# Sheet1.net
KiCad netlist of a schematic drawn in Altium Designer
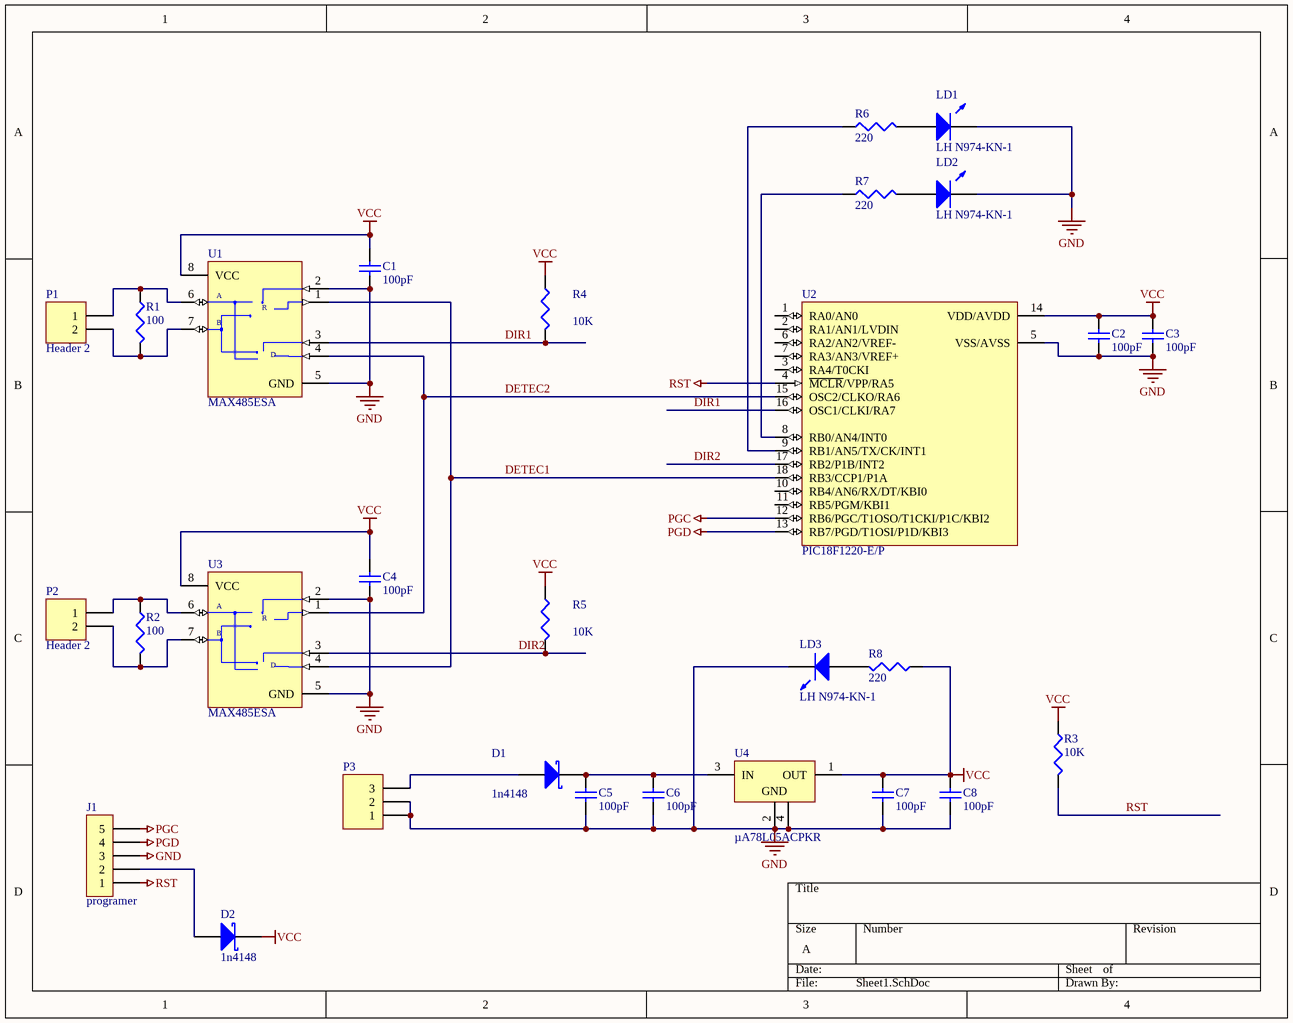
[diagram p0: Sheet1.SchDoc]

(export (version "E")
  (design (tool "Eeschema 10.0.6"))
  (components
    (comp (ref "C1")
      (value "100pF")
      (footprint "RESC2012L")
      (description "Capacitor (Semiconductor SIM Model)")
      (fields (field (name "Comment") "Cap Semi") (field (name "PUBLISHER") "Altium Limited"))
      (libsource (lib "Miscellaneous Devices") (part "Cap Semi"))
    )
    (comp (ref "C2")
      (value "100pF")
      (footprint "RESC2012L")
      (description "Capacitor (Semiconductor SIM Model)")
      (fields (field (name "Comment") "Cap Semi") (field (name "PUBLISHER") "Altium Limited"))
      (libsource (lib "Miscellaneous Devices") (part "Cap Semi"))
    )
    (comp (ref "C3")
      (value "100pF")
      (footprint "RESC2012L")
      (description "Capacitor (Semiconductor SIM Model)")
      (fields (field (name "Comment") "Cap Semi") (field (name "PUBLISHER") "Altium Limited"))
      (libsource (lib "Miscellaneous Devices") (part "Cap Semi"))
    )
    (comp (ref "C4")
      (value "100pF")
      (footprint "RESC2012L")
      (description "Capacitor (Semiconductor SIM Model)")
      (fields (field (name "Comment") "Cap Semi") (field (name "PUBLISHER") "Altium Limited"))
      (libsource (lib "Miscellaneous Devices") (part "Cap Semi"))
    )
    (comp (ref "C5")
      (value "100pF")
      (footprint "RESC2012L")
      (description "Capacitor (Semiconductor SIM Model)")
      (fields (field (name "Comment") "Cap Semi") (field (name "PUBLISHER") "Altium Limited"))
      (libsource (lib "Miscellaneous Devices") (part "Cap Semi"))
    )
    (comp (ref "C6")
      (value "100pF")
      (footprint "RESC2012L")
      (description "Capacitor (Semiconductor SIM Model)")
      (fields (field (name "Comment") "Cap Semi") (field (name "PUBLISHER") "Altium Limited"))
      (libsource (lib "Miscellaneous Devices") (part "Cap Semi"))
    )
    (comp (ref "C7")
      (value "100pF")
      (footprint "RESC2012L")
      (description "Capacitor (Semiconductor SIM Model)")
      (fields (field (name "Comment") "Cap Semi") (field (name "PUBLISHER") "Altium Limited"))
      (libsource (lib "Miscellaneous Devices") (part "Cap Semi"))
    )
    (comp (ref "C8")
      (value "100pF")
      (footprint "RESC2012L")
      (description "Capacitor (Semiconductor SIM Model)")
      (fields (field (name "Comment") "Cap Semi") (field (name "PUBLISHER") "Altium Limited"))
      (libsource (lib "Miscellaneous Devices") (part "Cap Semi"))
    )
    (comp (ref "D1")
      (value "1n4148")
      (footprint "CD3216-1206")
      (description "Schottky Diode")
      (fields (field (name "PUBLISHER") "Altium Limited"))
      (libsource (lib "Schlib1") (part "1N4148_SMD"))
    )
    (comp (ref "D2")
      (value "1n4148")
      (footprint "CD3216-1206")
      (description "Schottky Diode")
      (fields (field (name "PUBLISHER") "Altium Limited"))
      (libsource (lib "Schlib1") (part "1N4148_SMD"))
    )
    (comp (ref "J1")
      (value "programer")
      (footprint "CON5")
      (description "Connector")
      (libsource (lib "*") (part "CON5"))
    )
    (comp (ref "LD1")
      (value "LH N974-KN-1")
      (footprint "CD3216-1206")
      (description "LED CHIPLED 645NM RED DIFF 1206")
      (libsource (lib "AM335X_ZCZ") (part "LEDRED1206"))
    )
    (comp (ref "LD2")
      (value "LH N974-KN-1")
      (footprint "CD3216-1206")
      (description "LED CHIPLED 645NM RED DIFF 1206")
      (libsource (lib "AM335X_ZCZ") (part "LEDRED1206"))
    )
    (comp (ref "LD3")
      (value "LH N974-KN-1")
      (footprint "CD3216-1206")
      (description "LED CHIPLED 645NM RED DIFF 1206")
      (libsource (lib "AM335X_ZCZ") (part "LEDRED1206"))
    )
    (comp (ref "P1")
      (value "Header 2")
      (footprint "CON2")
      (description "Header, 2-Pin")
      (fields (field (name "PUBLISHER") "Altium Limited"))
      (libsource (lib "Miscellaneous Connectors") (part "Header 2"))
    )
    (comp (ref "P2")
      (value "Header 2")
      (footprint "CON2")
      (description "Header, 2-Pin")
      (fields (field (name "PUBLISHER") "Altium Limited"))
      (libsource (lib "Miscellaneous Connectors") (part "Header 2"))
    )
    (comp (ref "P3")
      (value "~")
      (footprint "CONP3")
      (description "Header, 3-Pin")
      (fields (field (name "PUBLISHER") "Altium Limited"))
      (libsource (lib "Miscellaneous Connectors") (part "Header 3"))
    )
    (comp (ref "R1")
      (value "100")
      (footprint "RESC2012L")
      (description "Resistor")
      (fields (field (name "Comment") "Res3") (field (name "PUBLISHER") "Altium Limited"))
      (libsource (lib "Miscellaneous Devices") (part "Res3"))
    )
    (comp (ref "R2")
      (value "100")
      (footprint "RESC2012L")
      (description "Resistor")
      (fields (field (name "Comment") "Res3") (field (name "PUBLISHER") "Altium Limited"))
      (libsource (lib "Miscellaneous Devices") (part "Res3"))
    )
    (comp (ref "R3")
      (value "10K")
      (footprint "RESC2012L")
      (description "Resistor")
      (fields (field (name "Comment") "Res3") (field (name "PUBLISHER") "Altium Limited"))
      (libsource (lib "Miscellaneous Devices") (part "Res3"))
    )
    (comp (ref "R4")
      (value "10K")
      (footprint "RESC2012L")
      (description "Resistor")
      (fields (field (name "Comment") "Res3") (field (name "PUBLISHER") "Altium Limited"))
      (libsource (lib "Miscellaneous Devices") (part "Res3"))
    )
    (comp (ref "R5")
      (value "10K")
      (footprint "RESC2012L")
      (description "Resistor")
      (fields (field (name "Comment") "Res3") (field (name "PUBLISHER") "Altium Limited"))
      (libsource (lib "Miscellaneous Devices") (part "Res3"))
    )
    (comp (ref "R6")
      (value "220")
      (footprint "RESC2012L")
      (description "Resistor")
      (fields (field (name "Comment") "Res3") (field (name "PUBLISHER") "Altium Limited"))
      (libsource (lib "Miscellaneous Devices") (part "Res3"))
    )
    (comp (ref "R7")
      (value "220")
      (footprint "RESC2012L")
      (description "Resistor")
      (fields (field (name "Comment") "Res3") (field (name "PUBLISHER") "Altium Limited"))
      (libsource (lib "Miscellaneous Devices") (part "Res3"))
    )
    (comp (ref "R8")
      (value "220")
      (footprint "RESC2012L")
      (description "Resistor")
      (fields (field (name "Comment") "Res3") (field (name "PUBLISHER") "Altium Limited"))
      (libsource (lib "Miscellaneous Devices") (part "Res3"))
    )
    (comp (ref "U1")
      (value "MAX485ESA")
      (footprint "NSO8_L")
      (description "Low-Power, Slew-Rate-Limited RS-485/RS-422 Transceiver")
      (fields (field (name "PUBLISHER") "Altium Limited"))
      (libsource (lib "Maxim Communication Transceiver") (part "MAX485ESA"))
    )
    (comp (ref "U2")
      (value "PIC18F1220-E/P")
      (footprint "PDIP300-P18")
      (fields (field (name "PUBLISHER") "Altium Limited"))
      (libsource (lib "Microchip Microcontroller 8-Bit PIC18") (part "PIC18F1220-E/P"))
    )
    (comp (ref "U3")
      (value "MAX485ESA")
      (footprint "NSO8_L")
      (description "Low-Power, Slew-Rate-Limited RS-485/RS-422 Transceiver")
      (fields (field (name "PUBLISHER") "Altium Limited"))
      (libsource (lib "Maxim Communication Transceiver") (part "MAX485ESA"))
    )
    (comp (ref "U4")
      (value "µA78L05ACPKR")
      (footprint "PK03")
      (description "Positive-Voltage Regulator")
      (fields (field (name "PUBLISHER") "Altium Limited"))
      (libsource (lib "Schlib1") (part "µA78L05ACPKR"))
    )
  )
  (nets
    (net (code "1") (name "/DETEC1") (class "Default")
      (node (ref "U1") (pin "1") (pinfunction "RO_1") (pintype "output"))
      (node (ref "U2") (pin "18") (pinfunction "RB3/CCP1/P1A_18") (pintype "bidirectional"))
      (node (ref "U3") (pin "4") (pinfunction "DI_4") (pintype "input"))
    )
    (net (code "2") (name "/DETEC2") (class "Default")
      (node (ref "U1") (pin "4") (pinfunction "DI_4") (pintype "input"))
      (node (ref "U2") (pin "15") (pinfunction "OSC2/CLKO/RA6_15") (pintype "bidirectional"))
      (node (ref "U3") (pin "1") (pinfunction "RO_1") (pintype "output"))
    )
    (net (code "3") (name "/DIR1") (class "Default")
      (node (ref "R4") (pin "2") (pinfunction "2_2") (pintype "passive"))
      (node (ref "U1") (pin "3") (pinfunction "DE_3") (pintype "input"))
      (node (ref "U2") (pin "16") (pinfunction "OSC1/CLKI/RA7_16") (pintype "bidirectional"))
    )
    (net (code "4") (name "/DIR2") (class "Default")
      (node (ref "R5") (pin "2") (pinfunction "2_2") (pintype "passive"))
      (node (ref "U2") (pin "17") (pinfunction "RB2/P1B/INT2_17") (pintype "bidirectional"))
      (node (ref "U3") (pin "3") (pinfunction "DE_3") (pintype "input"))
    )
    (net (code "5") (name "GND") (class "Default")
      (node (ref "C1") (pin "1") (pinfunction "1_1") (pintype "passive"))
      (node (ref "C2") (pin "1") (pinfunction "1_1") (pintype "passive"))
      (node (ref "C3") (pin "1") (pinfunction "1_1") (pintype "passive"))
      (node (ref "C4") (pin "1") (pinfunction "1_1") (pintype "passive"))
      (node (ref "C5") (pin "1") (pinfunction "1_1") (pintype "passive"))
      (node (ref "C6") (pin "1") (pinfunction "1_1") (pintype "passive"))
      (node (ref "C7") (pin "1") (pinfunction "1_1") (pintype "passive"))
      (node (ref "C8") (pin "1") (pinfunction "1_1") (pintype "passive"))
      (node (ref "J1") (pin "3") (pinfunction "3_3") (pintype "passive"))
      (node (ref "LD1") (pin "2") (pinfunction "K_2") (pintype "passive"))
      (node (ref "LD2") (pin "2") (pinfunction "K_2") (pintype "passive"))
      (node (ref "LD3") (pin "2") (pinfunction "K_2") (pintype "passive"))
      (node (ref "P3") (pin "1") (pinfunction "1_1") (pintype "passive"))
      (node (ref "P3") (pin "2") (pinfunction "2_2") (pintype "passive"))
      (node (ref "U1") (pin "2") (pinfunction "~{RE}_2") (pintype "input"))
      (node (ref "U1") (pin "5") (pinfunction "GND_5") (pintype "power_in"))
      (node (ref "U2") (pin "5") (pinfunction "VSS/AVSS_5") (pintype "power_in"))
      (node (ref "U3") (pin "2") (pinfunction "~{RE}_2") (pintype "input"))
      (node (ref "U3") (pin "5") (pinfunction "GND_5") (pintype "power_in"))
      (node (ref "U4") (pin "2") (pinfunction "GND_2") (pintype "power_in"))
      (node (ref "U4") (pin "4") (pinfunction "GND_4") (pintype "power_in"))
    )
    (net (code "6") (name "Net-(D1-A)") (class "Default")
      (node (ref "D1") (pin "1") (pinfunction "A_1") (pintype "passive"))
      (node (ref "P3") (pin "3") (pinfunction "3_3") (pintype "passive"))
    )
    (net (code "7") (name "Net-(D1-K)") (class "Default")
      (node (ref "C5") (pin "2") (pinfunction "2_2") (pintype "passive"))
      (node (ref "C6") (pin "2") (pinfunction "2_2") (pintype "passive"))
      (node (ref "D1") (pin "2") (pinfunction "K_2") (pintype "passive"))
      (node (ref "U4") (pin "3") (pinfunction "IN_3") (pintype "power_in"))
    )
    (net (code "8") (name "Net-(D2-A)") (class "Default")
      (node (ref "D2") (pin "1") (pinfunction "A_1") (pintype "passive"))
      (node (ref "J1") (pin "2") (pinfunction "2_2") (pintype "passive"))
    )
    (net (code "9") (name "Net-(LD1-A)") (class "Default")
      (node (ref "LD1") (pin "1") (pinfunction "A_1") (pintype "passive"))
      (node (ref "R6") (pin "2") (pinfunction "2_2") (pintype "passive"))
    )
    (net (code "10") (name "Net-(LD2-A)") (class "Default")
      (node (ref "LD2") (pin "1") (pinfunction "A_1") (pintype "passive"))
      (node (ref "R7") (pin "2") (pinfunction "2_2") (pintype "passive"))
    )
    (net (code "11") (name "Net-(LD3-A)") (class "Default")
      (node (ref "LD3") (pin "1") (pinfunction "A_1") (pintype "passive"))
      (node (ref "R8") (pin "2") (pinfunction "2_2") (pintype "passive"))
    )
    (net (code "12") (name "Net-(U1-A)") (class "Default")
      (node (ref "P1") (pin "1") (pinfunction "1_1") (pintype "passive"))
      (node (ref "R1") (pin "1") (pinfunction "1_1") (pintype "passive"))
      (node (ref "U1") (pin "6") (pinfunction "A_6") (pintype "bidirectional"))
    )
    (net (code "13") (name "Net-(U1-B)") (class "Default")
      (node (ref "P1") (pin "2") (pinfunction "2_2") (pintype "passive"))
      (node (ref "R1") (pin "2") (pinfunction "2_2") (pintype "passive"))
      (node (ref "U1") (pin "7") (pinfunction "B_7") (pintype "bidirectional"))
    )
    (net (code "14") (name "Net-(U2-RB0{slash}AN4{slash}INT0)") (class "Default")
      (node (ref "R7") (pin "1") (pinfunction "1_1") (pintype "passive"))
      (node (ref "U2") (pin "8") (pinfunction "RB0/AN4/INT0_8") (pintype "bidirectional"))
    )
    (net (code "15") (name "Net-(U2-RB1{slash}AN5{slash}TX{slash}CK{slash}INT1)") (class "Default")
      (node (ref "R6") (pin "1") (pinfunction "1_1") (pintype "passive"))
      (node (ref "U2") (pin "9") (pinfunction "RB1/AN5/TX/CK/INT1_9") (pintype "bidirectional"))
    )
    (net (code "16") (name "Net-(U3-A)") (class "Default")
      (node (ref "P2") (pin "1") (pinfunction "1_1") (pintype "passive"))
      (node (ref "R2") (pin "1") (pinfunction "1_1") (pintype "passive"))
      (node (ref "U3") (pin "6") (pinfunction "A_6") (pintype "bidirectional"))
    )
    (net (code "17") (name "Net-(U3-B)") (class "Default")
      (node (ref "P2") (pin "2") (pinfunction "2_2") (pintype "passive"))
      (node (ref "R2") (pin "2") (pinfunction "2_2") (pintype "passive"))
      (node (ref "U3") (pin "7") (pinfunction "B_7") (pintype "bidirectional"))
    )
    (net (code "18") (name "PGC") (class "Default")
      (node (ref "J1") (pin "5") (pinfunction "5_5") (pintype "passive"))
      (node (ref "U2") (pin "12") (pinfunction "RB6/PGC/T1OSO/T1CKI/P1C/KBI2_12") (pintype "bidirectional"))
    )
    (net (code "19") (name "PGD") (class "Default")
      (node (ref "J1") (pin "4") (pinfunction "4_4") (pintype "passive"))
      (node (ref "U2") (pin "13") (pinfunction "RB7/PGD/T1OSI/P1D/KBI3_13") (pintype "bidirectional"))
    )
    (net (code "20") (name "RST") (class "Default")
      (node (ref "J1") (pin "1") (pinfunction "1_1") (pintype "passive"))
      (node (ref "R3") (pin "2") (pinfunction "2_2") (pintype "passive"))
      (node (ref "U2") (pin "4") (pinfunction "~{MCLR}/VPP/RA5_4") (pintype "input"))
    )
    (net (code "21") (name "VCC") (class "Default")
      (node (ref "C1") (pin "2") (pinfunction "2_2") (pintype "passive"))
      (node (ref "C2") (pin "2") (pinfunction "2_2") (pintype "passive"))
      (node (ref "C3") (pin "2") (pinfunction "2_2") (pintype "passive"))
      (node (ref "C4") (pin "2") (pinfunction "2_2") (pintype "passive"))
      (node (ref "C7") (pin "2") (pinfunction "2_2") (pintype "passive"))
      (node (ref "C8") (pin "2") (pinfunction "2_2") (pintype "passive"))
      (node (ref "D2") (pin "2") (pinfunction "K_2") (pintype "passive"))
      (node (ref "R3") (pin "1") (pinfunction "1_1") (pintype "passive"))
      (node (ref "R4") (pin "1") (pinfunction "1_1") (pintype "passive"))
      (node (ref "R5") (pin "1") (pinfunction "1_1") (pintype "passive"))
      (node (ref "R8") (pin "1") (pinfunction "1_1") (pintype "passive"))
      (node (ref "U1") (pin "8") (pinfunction "VCC_8") (pintype "power_in"))
      (node (ref "U2") (pin "14") (pinfunction "VDD/AVDD_14") (pintype "power_in"))
      (node (ref "U3") (pin "8") (pinfunction "VCC_8") (pintype "power_in"))
      (node (ref "U4") (pin "1") (pinfunction "OUT_1") (pintype "power_in"))
    )
    (net (code "22") (name "unconnected-(U2-RA0{slash}AN0-Pad1)") (class "Default")
      (node (ref "U2") (pin "1") (pinfunction "RA0/AN0_1") (pintype "bidirectional"))
    )
    (net (code "23") (name "unconnected-(U2-RA1{slash}AN1{slash}LVDIN-Pad2)") (class "Default")
      (node (ref "U2") (pin "2") (pinfunction "RA1/AN1/LVDIN_2") (pintype "bidirectional"))
    )
    (net (code "24") (name "unconnected-(U2-RA2{slash}AN2{slash}VREF--Pad6)") (class "Default")
      (node (ref "U2") (pin "6") (pinfunction "RA2/AN2/VREF-_6") (pintype "bidirectional"))
    )
    (net (code "25") (name "unconnected-(U2-RA3{slash}AN3{slash}VREF+-Pad7)") (class "Default")
      (node (ref "U2") (pin "7") (pinfunction "RA3/AN3/VREF+_7") (pintype "bidirectional"))
    )
    (net (code "26") (name "unconnected-(U2-RA4{slash}T0CKI-Pad3)") (class "Default")
      (node (ref "U2") (pin "3") (pinfunction "RA4/T0CKI_3") (pintype "bidirectional"))
    )
    (net (code "27") (name "unconnected-(U2-RB4{slash}AN6{slash}RX{slash}DT{slash}KBI0-Pad10)") (class "Default")
      (node (ref "U2") (pin "10") (pinfunction "RB4/AN6/RX/DT/KBI0_10") (pintype "bidirectional"))
    )
    (net (code "28") (name "unconnected-(U2-RB5{slash}PGM{slash}KBI1-Pad11)") (class "Default")
      (node (ref "U2") (pin "11") (pinfunction "RB5/PGM/KBI1_11") (pintype "bidirectional"))
    )
  )
)
